# MCU.net
KiCad netlist of a schematic drawn in Altium Designer
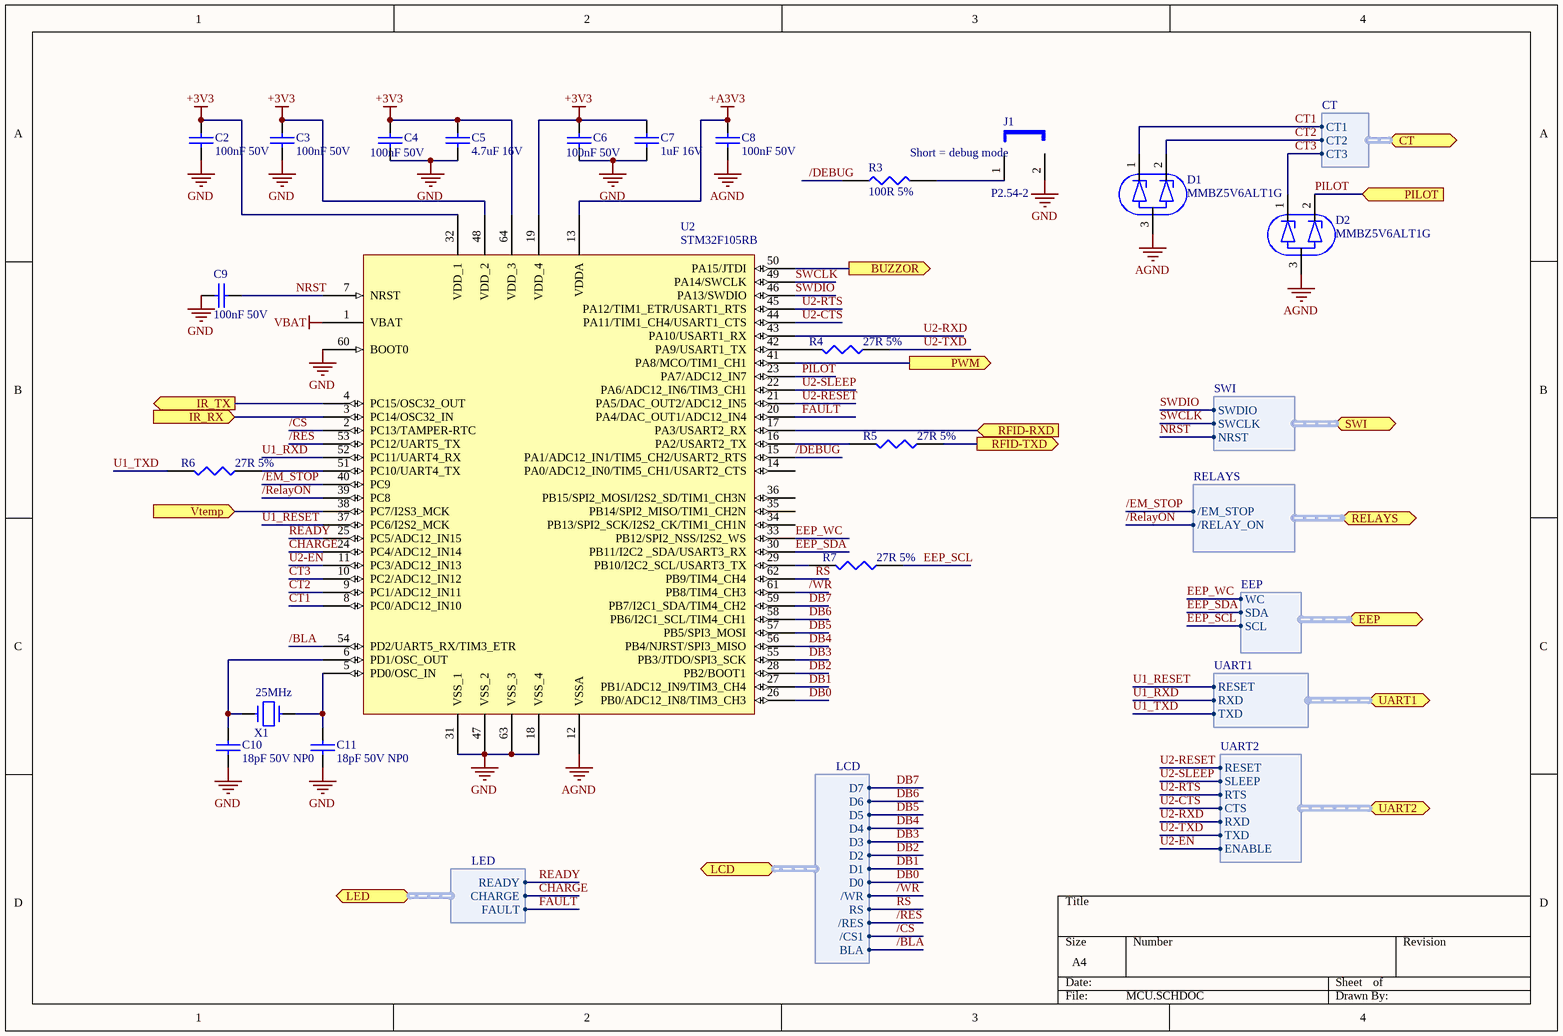
[diagram p0: MCU.SCHDOC]

(export (version "E")
  (design (tool "Eeschema 10.0.6"))
  (components
    (comp (ref "C2")
      (value "100nF 50V")
      (footprint "IPC-7352 Chip_Capacitor_N:CAPC2012N")
      (description "Capacitor")
      (libsource (lib "*") (part "CAP"))
    )
    (comp (ref "C3")
      (value "100nF 50V")
      (footprint "IPC-7352 Chip_Capacitor_N:CAPC2012N")
      (description "Capacitor")
      (libsource (lib "*") (part "CAP"))
    )
    (comp (ref "C4")
      (value "100nF 50V")
      (footprint "IPC-7352 Chip_Capacitor_N:CAPC2012N")
      (description "Capacitor")
      (libsource (lib "*") (part "CAP"))
    )
    (comp (ref "C5")
      (value "4.7uF 16V")
      (footprint "IPC-7352 Chip_Capacitor_N:CAPC2012N")
      (description "Capacitor")
      (libsource (lib "*") (part "CAP"))
    )
    (comp (ref "C6")
      (value "100nF 50V")
      (footprint "IPC-7352 Chip_Capacitor_N:CAPC2012N")
      (description "Capacitor")
      (libsource (lib "*") (part "CAP"))
    )
    (comp (ref "C7")
      (value "1uF 16V")
      (footprint "IPC-7352 Chip_Capacitor_N:CAPC2012N")
      (description "Capacitor")
      (libsource (lib "*") (part "CAP"))
    )
    (comp (ref "C8")
      (value "100nF 50V")
      (footprint "IPC-7352 Chip_Capacitor_N:CAPC2012N")
      (description "Capacitor")
      (libsource (lib "*") (part "CAP"))
    )
    (comp (ref "C9")
      (value "100nF 50V")
      (footprint "IPC-7352 Chip_Capacitor_N:CAPC2012N")
      (description "Capacitor")
      (libsource (lib "*") (part "CAP"))
    )
    (comp (ref "C10")
      (value "18pF 50V NP0")
      (footprint "IPC-7352 Chip_Capacitor_N:CAPC2012N")
      (libsource (lib "") (part "CAP_1"))
    )
    (comp (ref "C11")
      (value "18pF 50V NP0")
      (footprint "IPC-7352 Chip_Capacitor_N:CAPC2012N")
      (libsource (lib "") (part "CAP_1"))
    )
    (comp (ref "D1")
      (value "MMBZ5V6ALT1G")
      (footprint "SOT23_N:SOT23-3N")
      (description "ESD protection diode 3.3V")
      (fields (field (name "MANUFACTURER") "NXP"))
      (libsource (lib "UserSchlib") (part "PESD3V3S2UT"))
    )
    (comp (ref "D2")
      (value "MMBZ5V6ALT1G")
      (footprint "SOT23_N:SOT23-3N")
      (description "ESD protection diode 3.3V")
      (fields (field (name "MANUFACTURER") "NXP"))
      (libsource (lib "UserSchlib") (part "PESD3V3S2UT"))
    )
    (comp (ref "J1")
      (value "P2.54-2")
      (footprint "UserPcbLib:JP2-P2.54")
      (description "Jumper 2.54-2")
      (libsource (lib "*") (part "JUMPER"))
    )
    (comp (ref "R3")
      (value "100R 5%")
      (footprint "IPC-7352 Chip_Resistor_N:RESC2012N")
      (description "Resistor")
      (libsource (lib "*") (part "RES1"))
    )
    (comp (ref "R4")
      (value "27R 5%")
      (footprint "IPC-7352 Chip_Resistor_N:RESC2012N")
      (libsource (lib "*") (part "RES1"))
    )
    (comp (ref "R5")
      (value "27R 5%")
      (footprint "IPC-7352 Chip_Resistor_N:RESC2012N")
      (libsource (lib "*") (part "RES1"))
    )
    (comp (ref "R6")
      (value "27R 5%")
      (footprint "IPC-7352 Chip_Resistor_N:RESC2012N")
      (libsource (lib "*") (part "RES1"))
    )
    (comp (ref "R7")
      (value "27R 5%")
      (footprint "IPC-7352 Chip_Resistor_N:RESC2012N")
      (libsource (lib "*") (part "RES1"))
    )
    (comp (ref "U2")
      (value "STM32F105RB")
      (footprint "ST-Microelectronics Footprints:TQFP64_M")
      (description "ST Cortex M3 MCU 64 pins")
      (libsource (lib "UserSchlib") (part "STM32F105XX"))
    )
    (comp (ref "X1")
      (value "25MHz")
      (footprint "ATSM-49")
      (description "Crystal")
      (libsource (lib "*") (part "CRYSTAL"))
    )
  )
  (nets
    (net (code "9") (name "+3V3") (class "Default")
      (node (ref "C2") (pin "1") (pinfunction "1_1") (pintype "passive"))
      (node (ref "C3") (pin "1") (pinfunction "1_1") (pintype "passive"))
      (node (ref "C4") (pin "1") (pinfunction "1_1") (pintype "passive"))
      (node (ref "C5") (pin "1") (pinfunction "1_1") (pintype "passive"))
      (node (ref "C6") (pin "1") (pinfunction "1_1") (pintype "passive"))
      (node (ref "C7") (pin "1") (pinfunction "1_1") (pintype "passive"))
      (node (ref "U2") (pin "19") (pinfunction "VDD_4_19") (pintype "power_in"))
      (node (ref "U2") (pin "32") (pinfunction "VDD_1_32") (pintype "power_in"))
      (node (ref "U2") (pin "48") (pinfunction "VDD_2_48") (pintype "power_in"))
      (node (ref "U2") (pin "64") (pinfunction "VDD_3_64") (pintype "power_in"))
    )
    (net (code "10") (name "+A3V3") (class "Default")
      (node (ref "C8") (pin "1") (pinfunction "1_1") (pintype "passive"))
      (node (ref "U2") (pin "13") (pinfunction "VDDA_13") (pintype "power_in"))
    )
    (net (code "11") (name "/BUZZOR") (class "Default")
      (node (ref "U2") (pin "50") (pinfunction "PA15/JTDI_50") (pintype "bidirectional"))
    )
    (net (code "12") (name "/CHARGE") (class "Default")
      (node (ref "U2") (pin "24") (pinfunction "PC4/ADC12_IN14_24") (pintype "bidirectional"))
    )
    (net (code "13") (name "/CT1") (class "Default")
      (node (ref "D1") (pin "1") (pinfunction "1_1") (pintype "passive"))
      (node (ref "U2") (pin "8") (pinfunction "PC0/ADC12_IN10_8") (pintype "bidirectional"))
    )
    (net (code "14") (name "/CT2") (class "Default")
      (node (ref "D1") (pin "2") (pinfunction "2_2") (pintype "passive"))
      (node (ref "U2") (pin "9") (pinfunction "PC1/ADC12_IN11_9") (pintype "bidirectional"))
    )
    (net (code "15") (name "/CT3") (class "Default")
      (node (ref "D2") (pin "1") (pinfunction "1_1") (pintype "passive"))
      (node (ref "U2") (pin "10") (pinfunction "PC2/ADC12_IN12_10") (pintype "bidirectional"))
    )
    (net (code "16") (name "/DB0") (class "Default")
      (node (ref "U2") (pin "26") (pinfunction "PB0/ADC12_IN8/TIM3_CH3_26") (pintype "bidirectional"))
    )
    (net (code "17") (name "/DB1") (class "Default")
      (node (ref "U2") (pin "27") (pinfunction "PB1/ADC12_IN9/TIM3_CH4_27") (pintype "bidirectional"))
    )
    (net (code "18") (name "/DB2") (class "Default")
      (node (ref "U2") (pin "28") (pinfunction "PB2/BOOT1_28") (pintype "bidirectional"))
    )
    (net (code "19") (name "/DB3") (class "Default")
      (node (ref "U2") (pin "55") (pinfunction "PB3/JTDO/SPI3_SCK_55") (pintype "bidirectional"))
    )
    (net (code "20") (name "/DB4") (class "Default")
      (node (ref "U2") (pin "56") (pinfunction "PB4/NJRST/SPI3_MISO_56") (pintype "bidirectional"))
    )
    (net (code "21") (name "/DB5") (class "Default")
      (node (ref "U2") (pin "57") (pinfunction "PB5/SPI3_MOSI_57") (pintype "bidirectional"))
    )
    (net (code "22") (name "/DB6") (class "Default")
      (node (ref "U2") (pin "58") (pinfunction "PB6/I2C1_SCL/TIM4_CH1_58") (pintype "bidirectional"))
    )
    (net (code "23") (name "/DB7") (class "Default")
      (node (ref "U2") (pin "59") (pinfunction "PB7/I2C1_SDA/TIM4_CH2_59") (pintype "bidirectional"))
    )
    (net (code "24") (name "/EEP_SCL") (class "Default")
      (node (ref "R7") (pin "1") (pinfunction "1_1") (pintype "passive"))
    )
    (net (code "25") (name "/EEP_SDA") (class "Default")
      (node (ref "U2") (pin "30") (pinfunction "PB11/I2C2__SDA/USART3_RX_30") (pintype "bidirectional"))
    )
    (net (code "26") (name "/EEP_WC") (class "Default")
      (node (ref "U2") (pin "33") (pinfunction "PB12/SPI2_NSS/I2S2_WS_33") (pintype "bidirectional"))
    )
    (net (code "27") (name "/FAULT") (class "Default")
      (node (ref "U2") (pin "20") (pinfunction "PA4/DAC_OUT1/ADC12_IN4_20") (pintype "bidirectional"))
    )
    (net (code "28") (name "/IR_RX") (class "Default")
      (node (ref "U2") (pin "3") (pinfunction "PC14/OSC32_IN_3") (pintype "bidirectional"))
    )
    (net (code "29") (name "/IR_TX") (class "Default")
      (node (ref "U2") (pin "4") (pinfunction "PC15/OSC32_OUT_4") (pintype "bidirectional"))
    )
    (net (code "30") (name "/NRST") (class "Default")
      (node (ref "C9") (pin "1") (pinfunction "1_1") (pintype "passive"))
      (node (ref "U2") (pin "7") (pinfunction "NRST_7") (pintype "input"))
    )
    (net (code "31") (name "/PILOT") (class "Default")
      (node (ref "D2") (pin "2") (pinfunction "2_2") (pintype "passive"))
      (node (ref "U2") (pin "23") (pinfunction "PA7/ADC12_IN7_23") (pintype "bidirectional"))
    )
    (net (code "32") (name "/PWM") (class "Default")
      (node (ref "U2") (pin "41") (pinfunction "PA8/MCO/TIM1_CH1_41") (pintype "bidirectional"))
    )
    (net (code "33") (name "/READY") (class "Default")
      (node (ref "U2") (pin "25") (pinfunction "PC5/ADC12_IN15_25") (pintype "bidirectional"))
    )
    (net (code "34") (name "/RFID-RXD") (class "Default")
      (node (ref "U2") (pin "17") (pinfunction "PA3/USART2_RX_17") (pintype "bidirectional"))
    )
    (net (code "35") (name "/RFID-TXD") (class "Default")
      (node (ref "R5") (pin "1") (pinfunction "1_1") (pintype "passive"))
    )
    (net (code "36") (name "/RS") (class "Default")
      (node (ref "U2") (pin "62") (pinfunction "PB9/TIM4_CH4_62") (pintype "bidirectional"))
    )
    (net (code "37") (name "/SWCLK") (class "Default")
      (node (ref "U2") (pin "49") (pinfunction "PA14/SWCLK_49") (pintype "bidirectional"))
    )
    (net (code "38") (name "/SWDIO") (class "Default")
      (node (ref "U2") (pin "46") (pinfunction "PA13/SWDIO_46") (pintype "bidirectional"))
    )
    (net (code "39") (name "/U1_RESET") (class "Default")
      (node (ref "U2") (pin "37") (pinfunction "PC6/I2S2_MCK_37") (pintype "bidirectional"))
    )
    (net (code "40") (name "/U1_RXD") (class "Default")
      (node (ref "U2") (pin "52") (pinfunction "PC11/UART4_RX_52") (pintype "bidirectional"))
    )
    (net (code "41") (name "/U1_TXD") (class "Default")
      (node (ref "R6") (pin "2") (pinfunction "2_2") (pintype "passive"))
    )
    (net (code "42") (name "/U2-CTS") (class "Default")
      (node (ref "U2") (pin "44") (pinfunction "PA11/TIM1_CH4/USART1_CTS_44") (pintype "bidirectional"))
    )
    (net (code "43") (name "/U2-EN") (class "Default")
      (node (ref "U2") (pin "11") (pinfunction "PC3/ADC12_IN13_11") (pintype "bidirectional"))
    )
    (net (code "44") (name "/U2-RESET") (class "Default")
      (node (ref "U2") (pin "21") (pinfunction "PA5/DAC_OUT2/ADC12_IN5_21") (pintype "bidirectional"))
    )
    (net (code "45") (name "/U2-RTS") (class "Default")
      (node (ref "U2") (pin "45") (pinfunction "PA12/TIM1_ETR/USART1_RTS_45") (pintype "bidirectional"))
    )
    (net (code "46") (name "/U2-RXD") (class "Default")
      (node (ref "U2") (pin "43") (pinfunction "PA10/USART1_RX_43") (pintype "bidirectional"))
    )
    (net (code "47") (name "/U2-SLEEP") (class "Default")
      (node (ref "U2") (pin "22") (pinfunction "PA6/ADC12_IN6/TIM3_CH1_22") (pintype "bidirectional"))
    )
    (net (code "48") (name "/U2-TXD") (class "Default")
      (node (ref "R4") (pin "1") (pinfunction "1_1") (pintype "passive"))
    )
    (net (code "49") (name "/Vtemp") (class "Default")
      (node (ref "U2") (pin "38") (pinfunction "PC7/I2S3_MCK_38") (pintype "bidirectional"))
    )
    (net (code "58") (name "/{slash}BLA") (class "Default")
      (node (ref "U2") (pin "54") (pinfunction "PD2/UART5_RX/TIM3_ETR_54") (pintype "bidirectional"))
    )
    (net (code "59") (name "/{slash}CS") (class "Default")
      (node (ref "U2") (pin "2") (pinfunction "PC13/TAMPER-RTC_2") (pintype "bidirectional"))
    )
    (net (code "60") (name "/{slash}DEBUG") (class "Default")
      (node (ref "R3") (pin "1") (pinfunction "1_1") (pintype "passive"))
      (node (ref "U2") (pin "15") (pinfunction "PA1/ADC12_IN1/TIM5_CH2/USART2_RTS_15") (pintype "bidirectional"))
    )
    (net (code "61") (name "/{slash}EM_STOP") (class "Default")
      (node (ref "U2") (pin "40") (pinfunction "PC9_40") (pintype "bidirectional"))
    )
    (net (code "62") (name "/{slash}RES") (class "Default")
      (node (ref "U2") (pin "53") (pinfunction "PC12/UART5_TX_53") (pintype "bidirectional"))
    )
    (net (code "63") (name "/{slash}RelayON") (class "Default")
      (node (ref "U2") (pin "39") (pinfunction "PC8_39") (pintype "bidirectional"))
    )
    (net (code "64") (name "/{slash}WR") (class "Default")
      (node (ref "U2") (pin "61") (pinfunction "PB8/TIM4_CH3_61") (pintype "bidirectional"))
    )
    (net (code "65") (name "AGND") (class "Default")
      (node (ref "C8") (pin "2") (pinfunction "2_2") (pintype "passive"))
      (node (ref "D1") (pin "3") (pinfunction "3_3") (pintype "passive"))
      (node (ref "D2") (pin "3") (pinfunction "3_3") (pintype "passive"))
      (node (ref "U2") (pin "12") (pinfunction "VSSA_12") (pintype "power_in"))
    )
    (net (code "66") (name "GND") (class "Default")
      (node (ref "C10") (pin "1") (pintype "passive"))
      (node (ref "C11") (pin "1") (pintype "passive"))
      (node (ref "C2") (pin "2") (pinfunction "2_2") (pintype "passive"))
      (node (ref "C3") (pin "2") (pinfunction "2_2") (pintype "passive"))
      (node (ref "C4") (pin "2") (pinfunction "2_2") (pintype "passive"))
      (node (ref "C5") (pin "2") (pinfunction "2_2") (pintype "passive"))
      (node (ref "C6") (pin "2") (pinfunction "2_2") (pintype "passive"))
      (node (ref "C7") (pin "2") (pinfunction "2_2") (pintype "passive"))
      (node (ref "C9") (pin "2") (pinfunction "2_2") (pintype "passive"))
      (node (ref "J1") (pin "2") (pinfunction "2_2") (pintype "passive"))
      (node (ref "U2") (pin "18") (pinfunction "VSS_4_18") (pintype "power_in"))
      (node (ref "U2") (pin "31") (pinfunction "VSS_1_31") (pintype "power_in"))
      (node (ref "U2") (pin "47") (pinfunction "VSS_2_47") (pintype "power_in"))
      (node (ref "U2") (pin "60") (pinfunction "BOOT0_60") (pintype "input"))
      (node (ref "U2") (pin "63") (pinfunction "VSS_3_63") (pintype "power_in"))
    )
    (net (code "67") (name "Net-(J1-Pad1)") (class "Default")
      (node (ref "J1") (pin "1") (pinfunction "1_1") (pintype "passive"))
      (node (ref "R3") (pin "2") (pinfunction "2_2") (pintype "passive"))
    )
    (net (code "68") (name "Net-(U2-PA2{slash}USART2_TX)") (class "Default")
      (node (ref "R5") (pin "2") (pinfunction "2_2") (pintype "passive"))
      (node (ref "U2") (pin "16") (pinfunction "PA2/USART2_TX_16") (pintype "bidirectional"))
    )
    (net (code "69") (name "Net-(U2-PA9{slash}USART1_TX)") (class "Default")
      (node (ref "R4") (pin "2") (pinfunction "2_2") (pintype "passive"))
      (node (ref "U2") (pin "42") (pinfunction "PA9/USART1_TX_42") (pintype "bidirectional"))
    )
    (net (code "70") (name "Net-(U2-PB10{slash}I2C2_SCL{slash}USART3_TX)") (class "Default")
      (node (ref "R7") (pin "2") (pinfunction "2_2") (pintype "passive"))
      (node (ref "U2") (pin "29") (pinfunction "PB10/I2C2_SCL/USART3_TX_29") (pintype "bidirectional"))
    )
    (net (code "71") (name "Net-(U2-PC10{slash}UART4_TX)") (class "Default")
      (node (ref "R6") (pin "1") (pinfunction "1_1") (pintype "passive"))
      (node (ref "U2") (pin "51") (pinfunction "PC10/UART4_TX_51") (pintype "bidirectional"))
    )
    (net (code "72") (name "Net-(U2-PD0{slash}OSC_IN)") (class "Default")
      (node (ref "C11") (pin "2") (pintype "passive"))
      (node (ref "U2") (pin "5") (pinfunction "PD0/OSC_IN_5") (pintype "bidirectional"))
      (node (ref "X1") (pin "2") (pintype "passive"))
    )
    (net (code "73") (name "Net-(U2-PD1{slash}OSC_OUT)") (class "Default")
      (node (ref "C10") (pin "2") (pintype "passive"))
      (node (ref "U2") (pin "6") (pinfunction "PD1/OSC_OUT_6") (pintype "bidirectional"))
      (node (ref "X1") (pin "1") (pintype "passive"))
    )
    (net (code "74") (name "VBAT") (class "Default")
      (node (ref "U2") (pin "1") (pinfunction "VBAT_1") (pintype "power_in"))
    )
    (net (code "75") (name "unconnected-(U2-PA0{slash}ADC12_IN0{slash}TIM5_CH1{slash}USART2_CTS-Pad14)") (class "Default")
      (node (ref "U2") (pin "14") (pinfunction "PA0/ADC12_IN0/TIM5_CH1/USART2_CTS_14") (pintype "bidirectional"))
    )
    (net (code "76") (name "unconnected-(U2-PB13{slash}SPI2_SCK{slash}I2S2_CK{slash}TIM1_CH1N-Pad34)") (class "Default")
      (node (ref "U2") (pin "34") (pinfunction "PB13/SPI2_SCK/I2S2_CK/TIM1_CH1N_34") (pintype "bidirectional"))
    )
    (net (code "77") (name "unconnected-(U2-PB14{slash}SPI2_MISO{slash}TIM1_CH2N-Pad35)") (class "Default")
      (node (ref "U2") (pin "35") (pinfunction "PB14/SPI2_MISO/TIM1_CH2N_35") (pintype "bidirectional"))
    )
    (net (code "78") (name "unconnected-(U2-PB15{slash}SPI2_MOSI{slash}I2S2_SD{slash}TIM1_CH3N-Pad36)") (class "Default")
      (node (ref "U2") (pin "36") (pinfunction "PB15/SPI2_MOSI/I2S2_SD/TIM1_CH3N_36") (pintype "bidirectional"))
    )
  )
)
